# design.net
KiCad netlist of a schematic drawn in EasyEDA Pro
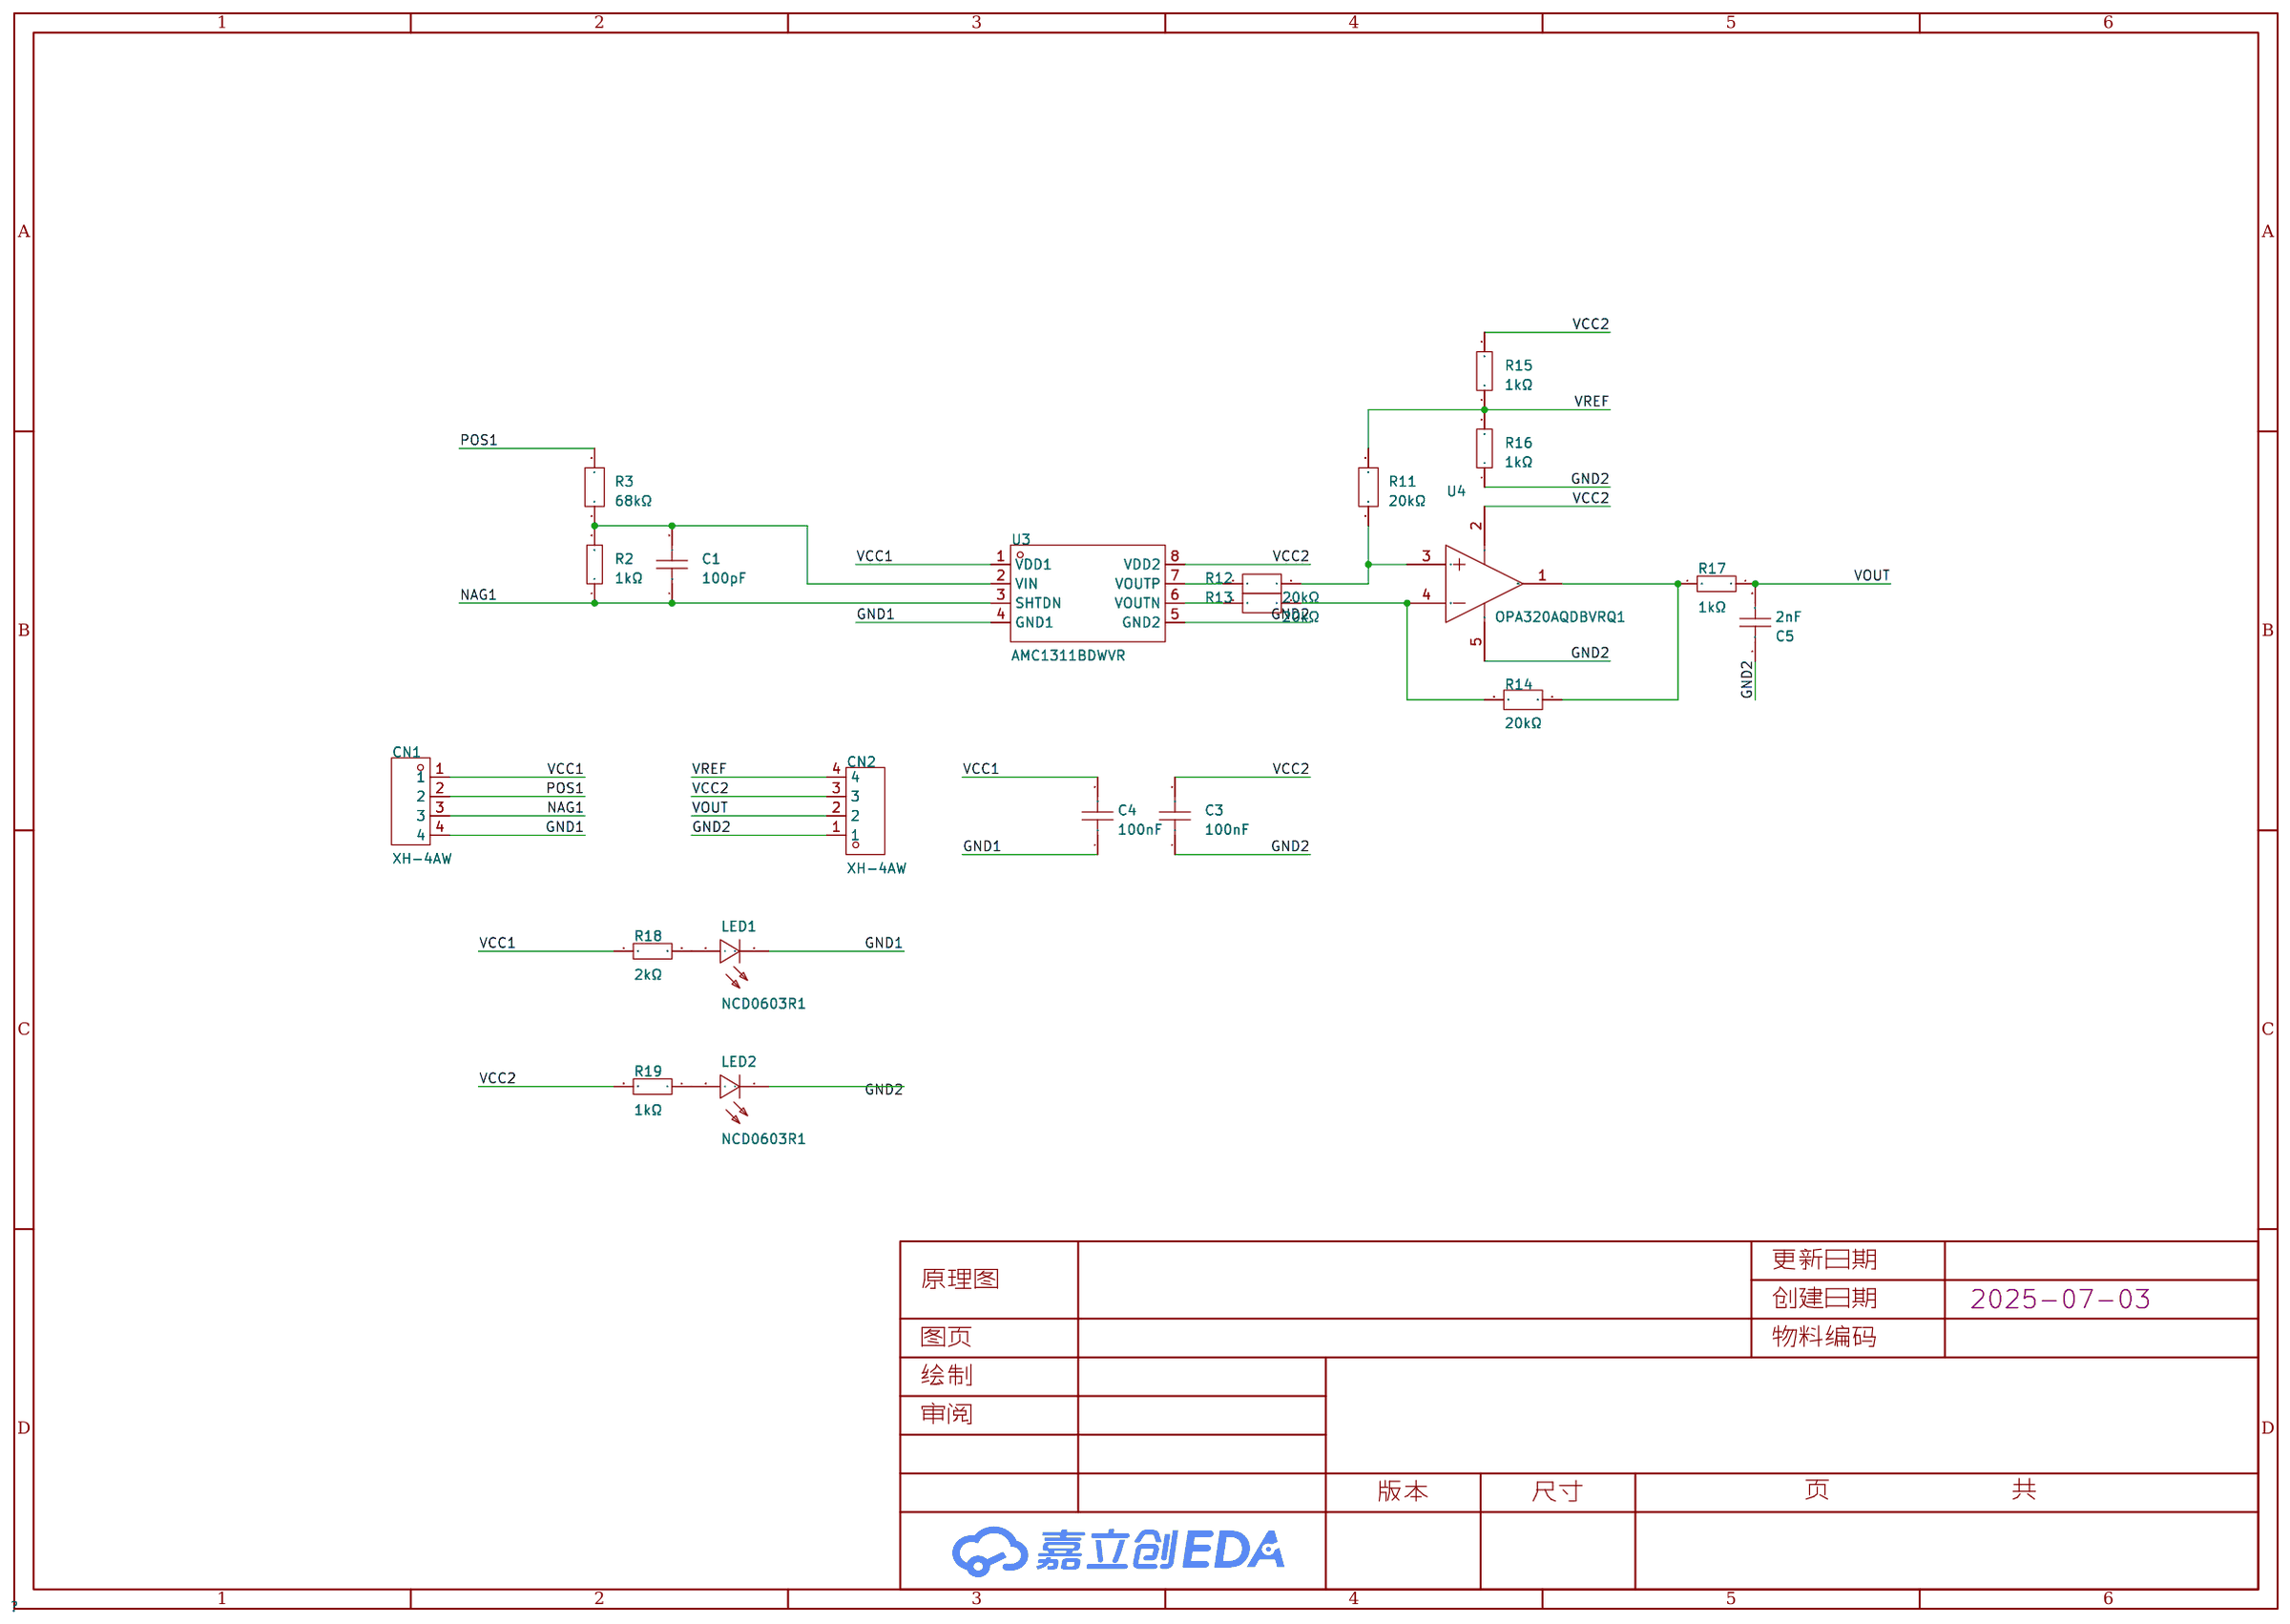
[diagram p0: schematic sheet]

(export (version "E")
  (design (tool "Eeschema 10.0.6"))
  (components
    (comp (ref "C1")
      (value "100pF")
      (footprint "easyedapro:C0603")
      (description "容值:100pF;精度:±1%;额定电压:50V;材质(温度系数):NP0;")
      (fields
        (field (name "Manufacturer Part") "CC0603FRNPO9BN101")
        (field (name "Manufacturer") "YAGEO(国巨)")
      )
      (libsource (lib "easyedapro") (part "CC0603FRNPO9BN101"))
    )
    (comp (ref "C3")
      (value "100nF")
      (footprint "easyedapro:C0603")
      (description "容值:100nF;精度:±10%;额定电压:50V;材质(温度系数):X7R;")
      (fields
        (field (name "Manufacturer Part") "CL10B104KB8NNNC")
        (field (name "Manufacturer") "SAMSUNG(三星)")
      )
      (libsource (lib "easyedapro") (part "CL10B104KB8NNNC"))
    )
    (comp (ref "C4")
      (value "100nF")
      (footprint "easyedapro:C0603")
      (description "容值:100nF;精度:±10%;额定电压:50V;材质(温度系数):X7R;")
      (fields
        (field (name "Manufacturer Part") "CL10B104KB8NNNC")
        (field (name "Manufacturer") "SAMSUNG(三星)")
      )
      (libsource (lib "easyedapro") (part "CL10B104KB8NNNC"))
    )
    (comp (ref "C5")
      (value "2nF")
      (footprint "easyedapro:C0603")
      (description "容值:2nF;精度:±10%;额定电压:50V;材质(温度系数):X7R;")
      (fields
        (field (name "Manufacturer Part") "CC0603KRX7R9BB202")
        (field (name "Manufacturer") "YAGEO(国巨)")
      )
      (libsource (lib "easyedapro") (part "CC0603KRX7R9BB202"))
    )
    (comp (ref "CN1")
      (value "XH-4AW")
      (footprint "easyedapro:CONN-TH_XH-4AW")
      (fields (field (name "Manufacturer") "HCTL(华灿天禄)"))
      (libsource (lib "easyedapro") (part "XH-4AW_C2908613"))
    )
    (comp (ref "CN2")
      (value "XH-4AW")
      (footprint "easyedapro:CONN-TH_XH-4AW")
      (fields (field (name "Manufacturer") "HCTL(华灿天禄)"))
      (libsource (lib "easyedapro") (part "XH-4AW_C2908613"))
    )
    (comp (ref "LED1")
      (value "NCD0603R1")
      (footprint "easyedapro:LED0603-RD_RED")
      (fields (field (name "Manufacturer") "国星光电"))
      (libsource (lib "easyedapro") (part "FC-DA1608HRK-620D"))
    )
    (comp (ref "LED2")
      (value "NCD0603R1")
      (footprint "easyedapro:LED0603-RD_RED")
      (fields (field (name "Manufacturer") "国星光电"))
      (libsource (lib "easyedapro") (part "FC-DA1608HRK-620D"))
    )
    (comp (ref "R2")
      (value "1kΩ")
      (footprint "easyedapro:R0603")
      (description "电阻类型:薄膜电阻;阻值:1kΩ;精度:±0.1%;功率:100mW;最大工作电压:75V;温度系数:±25ppm/°C;")
      (fields (field (name "Manufacturer Part") "RT0603BRD071KL") (field (name "Manufacturer") "YAGEO(国巨)"))
      (libsource (lib "easyedapro") (part "RT0603BRD071KL"))
    )
    (comp (ref "R3")
      (value "68kΩ")
      (footprint "easyedapro:R0603")
      (description "电阻类型:薄膜电阻;阻值:68kΩ;精度:±0.1%;功率:100mW;最大工作电压:75V;温度系数:±25ppm/°C;")
      (fields (field (name "Manufacturer Part") "RT0603BRD0768KL") (field (name "Manufacturer") "YAGEO(国巨)"))
      (libsource (lib "easyedapro") (part "RT0603BRD0768KL"))
    )
    (comp (ref "R11")
      (value "20kΩ")
      (footprint "easyedapro:R0603")
      (description "电阻类型:薄膜电阻;阻值:20kΩ;精度:±0.1%;功率:100mW;最大工作电压:75V;温度系数:±25ppm/°C;")
      (fields (field (name "Manufacturer Part") "RT0603BRD0720KL") (field (name "Manufacturer") "YAGEO(国巨)"))
      (libsource (lib "easyedapro") (part "RT0603BRD0720KL"))
    )
    (comp (ref "R12")
      (value "20kΩ")
      (footprint "easyedapro:R0603")
      (description "电阻类型:薄膜电阻;阻值:20kΩ;精度:±0.1%;功率:100mW;最大工作电压:75V;温度系数:±25ppm/°C;")
      (fields (field (name "Manufacturer Part") "RT0603BRD0720KL") (field (name "Manufacturer") "YAGEO(国巨)"))
      (libsource (lib "easyedapro") (part "RT0603BRD0720KL"))
    )
    (comp (ref "R13")
      (value "20kΩ")
      (footprint "easyedapro:R0603")
      (description "电阻类型:薄膜电阻;阻值:20kΩ;精度:±0.1%;功率:100mW;最大工作电压:75V;温度系数:±25ppm/°C;")
      (fields (field (name "Manufacturer Part") "RT0603BRD0720KL") (field (name "Manufacturer") "YAGEO(国巨)"))
      (libsource (lib "easyedapro") (part "RT0603BRD0720KL"))
    )
    (comp (ref "R14")
      (value "20kΩ")
      (footprint "easyedapro:R0603")
      (description "电阻类型:薄膜电阻;阻值:20kΩ;精度:±0.1%;功率:100mW;最大工作电压:75V;温度系数:±25ppm/°C;")
      (fields (field (name "Manufacturer Part") "RT0603BRD0720KL") (field (name "Manufacturer") "YAGEO(国巨)"))
      (libsource (lib "easyedapro") (part "RT0603BRD0720KL"))
    )
    (comp (ref "R15")
      (value "1kΩ")
      (footprint "easyedapro:R0603")
      (description "电阻类型:薄膜电阻;阻值:1kΩ;精度:±0.1%;功率:100mW;最大工作电压:75V;温度系数:±25ppm/°C;")
      (fields (field (name "Manufacturer Part") "RT0603BRD071KL") (field (name "Manufacturer") "YAGEO(国巨)"))
      (libsource (lib "easyedapro") (part "RT0603BRD071KL"))
    )
    (comp (ref "R16")
      (value "1kΩ")
      (footprint "easyedapro:R0603")
      (description "电阻类型:薄膜电阻;阻值:1kΩ;精度:±0.1%;功率:100mW;最大工作电压:75V;温度系数:±25ppm/°C;")
      (fields (field (name "Manufacturer Part") "RT0603BRD071KL") (field (name "Manufacturer") "YAGEO(国巨)"))
      (libsource (lib "easyedapro") (part "RT0603BRD071KL"))
    )
    (comp (ref "R17")
      (value "1kΩ")
      (footprint "easyedapro:R0603")
      (description "电阻类型:薄膜电阻;阻值:1kΩ;精度:±0.1%;功率:100mW;最大工作电压:75V;温度系数:±25ppm/°C;")
      (fields (field (name "Manufacturer Part") "RT0603BRD071KL") (field (name "Manufacturer") "YAGEO(国巨)"))
      (libsource (lib "easyedapro") (part "RT0603BRD071KL"))
    )
    (comp (ref "R18")
      (value "2kΩ")
      (footprint "easyedapro:R0603")
      (description "电阻类型:厚膜电阻;阻值:2kΩ;精度:±1%;功率:100mW;最大工作电压:75V;温度系数:±100ppm/°C;")
      (fields
        (field (name "Manufacturer Part") "0603WAF2001T5E")
        (field (name "Manufacturer") "UNI-ROYAL(厚声)")
      )
      (libsource (lib "easyedapro") (part "0603WAF2001T5E"))
    )
    (comp (ref "R19")
      (value "1kΩ")
      (footprint "easyedapro:R0603")
      (description "电阻类型:薄膜电阻;阻值:1kΩ;精度:±0.1%;功率:100mW;最大工作电压:75V;温度系数:±25ppm/°C;")
      (fields (field (name "Manufacturer Part") "RT0603BRD071KL") (field (name "Manufacturer") "YAGEO(国巨)"))
      (libsource (lib "easyedapro") (part "RT0603BRD071KL"))
    )
    (comp (ref "U3")
      (value "AMC1311BDWVR")
      (footprint "easyedapro:SOIC-8_L7.5-W5.9-P1.27-LS11.5-BL")
      (description "AMC1311 2V 输入、精密电压检测增强型隔离式放大器")
      (fields (field (name "Manufacturer") "TI(德州仪器)"))
      (libsource (lib "easyedapro") (part "AMC1311BDWVR"))
    )
    (comp (ref "U4")
      (value "OPA320AQDBVRQ1")
      (footprint "easyedapro:SOT-23-5_L2.9-W1.6-P0.95-LS2.8-BR")
      (description "放大器数:单路;增益带宽积(GBP):20MHz;输入偏置电流(Ib):0.2pA;压摆率(SR):10V/us;带宽(-3db):-;轨到轨:-;")
      (fields (field (name "Manufacturer") "TI(德州仪器)"))
      (libsource (lib "easyedapro") (part "OPA320AQDBVRQ1"))
    )
  )
  (nets
    (net (code "1") (name "/GND1") (class "Default")
      (node (ref "C4") (pin "1") (pinfunction "1_1") (pintype "unspecified"))
      (node (ref "CN1") (pin "4") (pinfunction "4_4") (pintype "unspecified"))
      (node (ref "LED1") (pin "1") (pinfunction "K_1") (pintype "input"))
      (node (ref "U3") (pin "4") (pinfunction "GND1_4") (pintype "unspecified"))
    )
    (net (code "2") (name "/GND2") (class "Default")
      (node (ref "C3") (pin "1") (pinfunction "1_1") (pintype "unspecified"))
      (node (ref "C5") (pin "1") (pinfunction "1_1") (pintype "unspecified"))
      (node (ref "CN2") (pin "1") (pinfunction "1_1") (pintype "unspecified"))
      (node (ref "LED2") (pin "1") (pinfunction "K_1") (pintype "input"))
      (node (ref "R16") (pin "1") (pinfunction "1_1") (pintype "input"))
      (node (ref "U3") (pin "5") (pinfunction "GND2_5") (pintype "unspecified"))
      (node (ref "U4") (pin "5") (pinfunction "V+_5") (pintype "unspecified"))
    )
    (net (code "3") (name "/NAG1") (class "Default")
      (node (ref "C1") (pin "1") (pinfunction "1_1") (pintype "unspecified"))
      (node (ref "CN1") (pin "3") (pinfunction "3_3") (pintype "unspecified"))
      (node (ref "R2") (pin "1") (pinfunction "1_1") (pintype "input"))
      (node (ref "U3") (pin "3") (pinfunction "SHTDN_3") (pintype "unspecified"))
    )
    (net (code "4") (name "/POS1") (class "Default")
      (node (ref "CN1") (pin "2") (pinfunction "2_2") (pintype "unspecified"))
      (node (ref "R3") (pin "2") (pinfunction "2_2") (pintype "unspecified"))
    )
    (net (code "5") (name "/VCC1") (class "Default")
      (node (ref "C4") (pin "2") (pinfunction "2_2") (pintype "unspecified"))
      (node (ref "CN1") (pin "1") (pinfunction "1_1") (pintype "unspecified"))
      (node (ref "R18") (pin "1") (pinfunction "1_1") (pintype "input"))
      (node (ref "U3") (pin "1") (pinfunction "VDD1_1") (pintype "unspecified"))
    )
    (net (code "6") (name "/VCC2") (class "Default")
      (node (ref "C3") (pin "2") (pinfunction "2_2") (pintype "unspecified"))
      (node (ref "CN2") (pin "3") (pinfunction "3_3") (pintype "unspecified"))
      (node (ref "R15") (pin "2") (pinfunction "2_2") (pintype "input"))
      (node (ref "R19") (pin "2") (pinfunction "2_2") (pintype "input"))
      (node (ref "U3") (pin "8") (pinfunction "VDD2_8") (pintype "unspecified"))
      (node (ref "U4") (pin "2") (pinfunction "V-_2") (pintype "unspecified"))
    )
    (net (code "7") (name "/VOUT") (class "Default")
      (node (ref "C5") (pin "2") (pinfunction "2_2") (pintype "unspecified"))
      (node (ref "CN2") (pin "2") (pinfunction "2_2") (pintype "unspecified"))
      (node (ref "R17") (pin "1") (pinfunction "1_1") (pintype "input"))
    )
    (net (code "8") (name "/VREF") (class "Default")
      (node (ref "CN2") (pin "4") (pinfunction "4_4") (pintype "unspecified"))
      (node (ref "R11") (pin "2") (pinfunction "2_2") (pintype "unspecified"))
      (node (ref "R15") (pin "1") (pinfunction "1_1") (pintype "input"))
      (node (ref "R16") (pin "2") (pinfunction "2_2") (pintype "input"))
    )
    (net (code "9") (name "Net-(LED1-A)") (class "Default")
      (node (ref "LED1") (pin "2") (pinfunction "A_2") (pintype "input"))
      (node (ref "R18") (pin "2") (pinfunction "2_2") (pintype "input"))
    )
    (net (code "10") (name "Net-(LED2-A)") (class "Default")
      (node (ref "LED2") (pin "2") (pinfunction "A_2") (pintype "input"))
      (node (ref "R19") (pin "1") (pinfunction "1_1") (pintype "input"))
    )
    (net (code "11") (name "Net-(U3-VIN)") (class "Default")
      (node (ref "C1") (pin "2") (pinfunction "2_2") (pintype "unspecified"))
      (node (ref "R2") (pin "2") (pinfunction "2_2") (pintype "input"))
      (node (ref "R3") (pin "1") (pinfunction "1_1") (pintype "unspecified"))
      (node (ref "U3") (pin "2") (pinfunction "VIN_2") (pintype "unspecified"))
    )
    (net (code "12") (name "Net-(U3-VOUTN)") (class "Default")
      (node (ref "R13") (pin "2") (pinfunction "2_2") (pintype "unspecified"))
      (node (ref "U3") (pin "6") (pinfunction "VOUTN_6") (pintype "unspecified"))
    )
    (net (code "13") (name "Net-(U3-VOUTP)") (class "Default")
      (node (ref "R12") (pin "2") (pinfunction "2_2") (pintype "unspecified"))
      (node (ref "U3") (pin "7") (pinfunction "VOUTP_7") (pintype "unspecified"))
    )
    (net (code "14") (name "Net-(U4-+IN)") (class "Default")
      (node (ref "R11") (pin "1") (pinfunction "1_1") (pintype "unspecified"))
      (node (ref "R12") (pin "1") (pinfunction "1_1") (pintype "unspecified"))
      (node (ref "U4") (pin "3") (pinfunction "+IN_3") (pintype "unspecified"))
    )
    (net (code "15") (name "Net-(U4--IN)") (class "Default")
      (node (ref "R13") (pin "1") (pinfunction "1_1") (pintype "unspecified"))
      (node (ref "R14") (pin "2") (pinfunction "2_2") (pintype "unspecified"))
      (node (ref "U4") (pin "4") (pinfunction "-IN_4") (pintype "unspecified"))
    )
    (net (code "16") (name "Net-(U4-OUT)") (class "Default")
      (node (ref "R14") (pin "1") (pinfunction "1_1") (pintype "unspecified"))
      (node (ref "R17") (pin "2") (pinfunction "2_2") (pintype "input"))
      (node (ref "U4") (pin "1") (pinfunction "OUT_1") (pintype "output"))
    )
  )
)
